# Power.net
KiCad netlist of a schematic drawn in Altium Designer
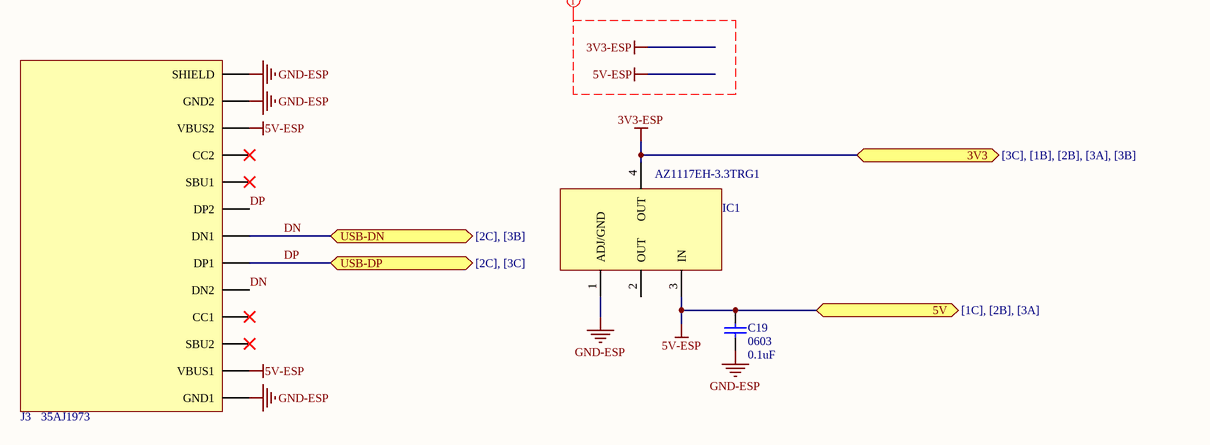
[diagram p0: Power.SchDoc]

(export (version "E")
  (design (tool "Eeschema 10.0.6"))
  (components
    (comp (ref "C19")
      (value "0.1uF")
      (footprint "SMD-CAP-0603-YAGEO")
      (description "0603 0.1 uF 16 V ±10 % Tolerance X7R SMT Multilayer Ceramic Capacitor")
      (fields
        (field (name "MANUFACTURER") "Yageo")
        (field (name "MANUFACTURER PART NUMBER") "CC0603KRX7R7BB104")
        (field (name "PACKAGE") "0603")
        (field (name "DESIGNER") "TVBac")
      )
      (libsource (lib "Capacitors") (part "CAP; 0.1uF; 16V; 0603; SMD; CC0603KRX7R7BB104"))
    )
    (comp (ref "IC1")
      (value "Linear Voltage Regulator IC Positive Fixed 1 Output 1A SOT-223-3")
      (footprint "IC:SOT-223-3-DI")
      (description "Linear Voltage Regulator IC 1 Output 1A SOT-223")
      (fields
        (field (name "MF") "Diodes Inc.")
        (field (name "MP") "AZ1117EH-3.3TRG1")
        (field (name "DESIGNER") "TVBac")
      )
      (libsource (lib "IC") (part "LDO; 3V3; 1A; SMD; AZ1117EH-3.3TRG1"))
    )
    (comp (ref "J3")
      (value "USB-C (USB TYPE-C) USB 2.0 Receptacle Connector 24 (16+8 Dummy) Position Surface Mount, Right Angle; Through Hole")
      (footprint "TYPE-C-HOR-RECEPTACLE-24PIN-MOLEX")
      (description "USB Connector, 16 Contact(s), Female, Right Angle, Surface Mount Terminal, Locking, Receptacle")
      (fields
        (field (name "SUPPLIER PART NUMBER") "35AJ1973")
        (field (name "MANUFACTURER") "Molex")
        (field (name "MANUFACTURER PART NUMBER") "217179-0001")
        (field (name "DESIGNER") "TVBac")
      )
      (libsource (lib "Socket") (part "Type-C; USB; HOR; RECEPTACLE;  24PIN; 217179-0001"))
    )
  )
  (nets
    (net (code "1") (name "/DN") (class "Default")
      (node (ref "J3") (pin "A7") (pinfunction "DN1_A7") (pintype "passive"))
      (node (ref "J3") (pin "B7") (pinfunction "DN2_B7") (pintype "passive"))
    )
    (net (code "2") (name "/DP") (class "Default")
      (node (ref "J3") (pin "A6") (pinfunction "DP1_A6") (pintype "passive"))
      (node (ref "J3") (pin "B6") (pinfunction "DP2_B6") (pintype "passive"))
    )
    (net (code "3") (name "3V3-ESP") (class "Default")
      (node (ref "IC1") (pin "4") (pinfunction "OUT_4") (pintype "passive"))
    )
    (net (code "4") (name "5V-ESP") (class "Default")
      (node (ref "C19") (pin "2") (pinfunction "2_2") (pintype "passive"))
      (node (ref "IC1") (pin "3") (pinfunction "IN_3") (pintype "passive"))
      (node (ref "J3") (pin "A4B9") (pinfunction "VBUS1_A4B9") (pintype "passive"))
      (node (ref "J3") (pin "B4A9") (pinfunction "VBUS2_B4A9") (pintype "passive"))
    )
    (net (code "5") (name "GND-ESP") (class "Default")
      (node (ref "C19") (pin "1") (pinfunction "1_1") (pintype "passive"))
      (node (ref "IC1") (pin "1") (pinfunction "ADJ/GND_1") (pintype "passive"))
      (node (ref "J3") (pin "A1B12") (pinfunction "GND1_A1B12") (pintype "passive"))
      (node (ref "J3") (pin "B1A12") (pinfunction "GND2_B1A12") (pintype "passive"))
      (node (ref "J3") (pin "SHIELD") (pinfunction "SHIELD_SHIELD") (pintype "passive"))
    )
    (net (code "6") (name "unconnected-(IC1-OUT-Pad2)") (class "Default")
      (node (ref "IC1") (pin "2") (pinfunction "OUT_2") (pintype "passive"))
    )
    (net (code "7") (name "unconnected-(J3-CC1-PadA5)") (class "Default")
      (node (ref "J3") (pin "A5") (pinfunction "CC1_A5") (pintype "passive+no_connect"))
    )
    (net (code "8") (name "unconnected-(J3-CC2-PadB5)") (class "Default")
      (node (ref "J3") (pin "B5") (pinfunction "CC2_B5") (pintype "passive+no_connect"))
    )
    (net (code "9") (name "unconnected-(J3-SBU1-PadA8)") (class "Default")
      (node (ref "J3") (pin "A8") (pinfunction "SBU1_A8") (pintype "passive+no_connect"))
    )
    (net (code "10") (name "unconnected-(J3-SBU2-PadB8)") (class "Default")
      (node (ref "J3") (pin "B8") (pinfunction "SBU2_B8") (pintype "passive+no_connect"))
    )
  )
)
